# M-LVDS_PHY.net
KiCad netlist of a schematic drawn in Altium Designer
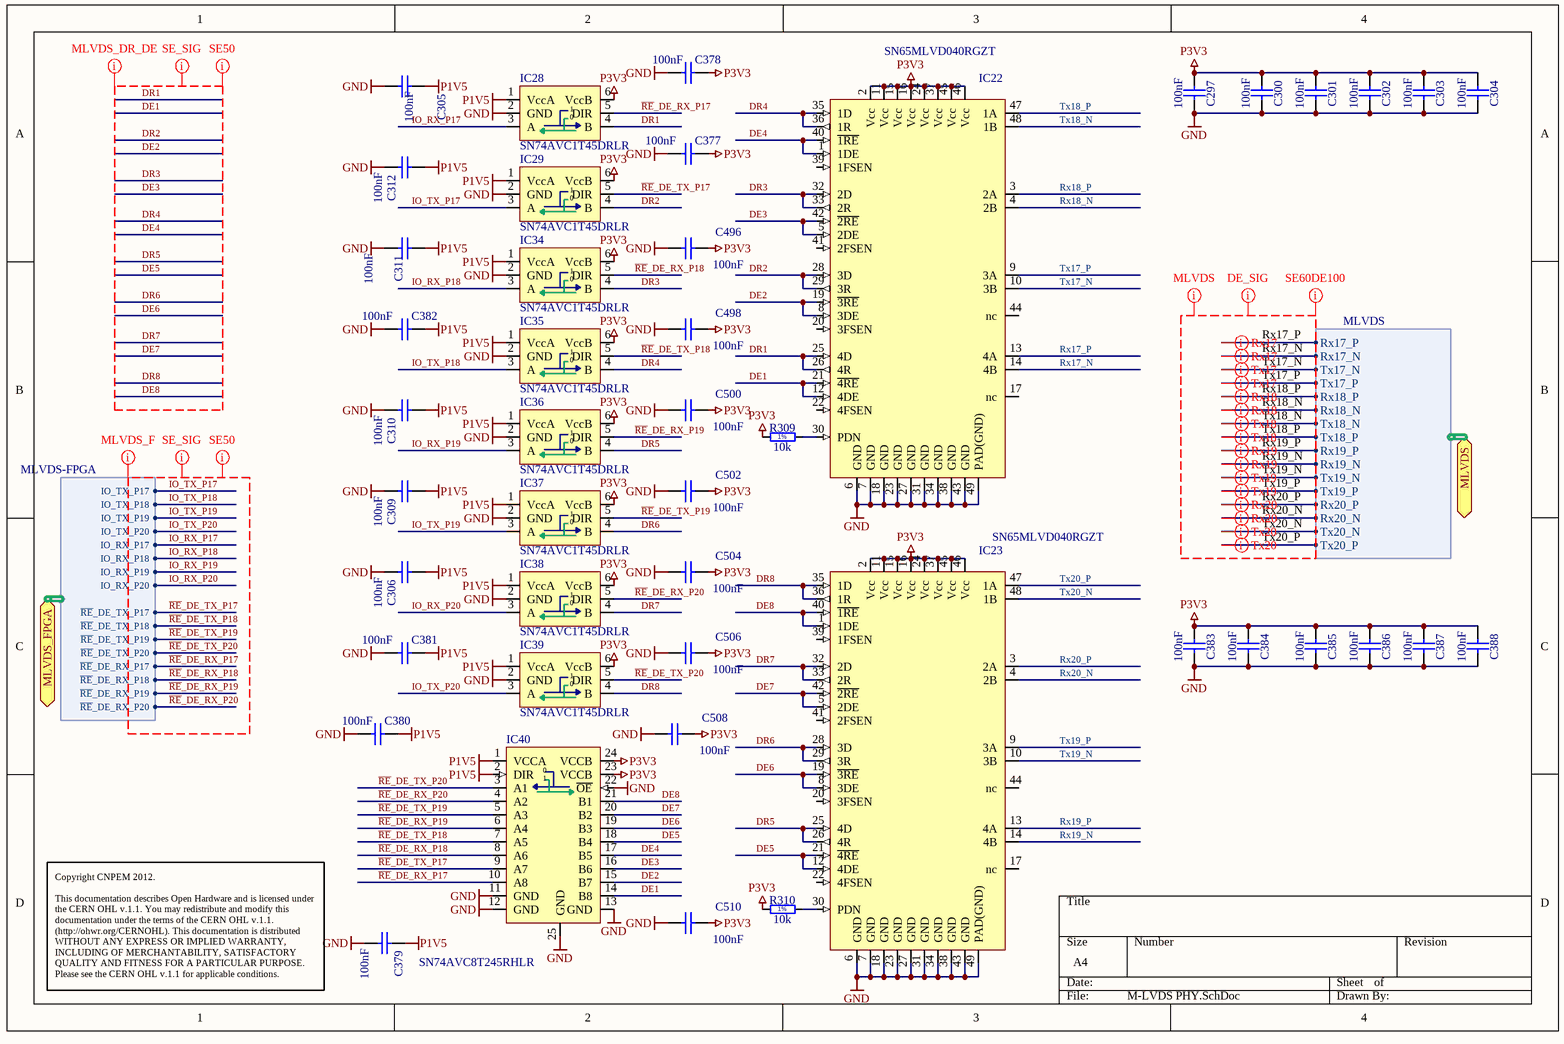
[diagram p0: M-LVDS PHY.SchDoc]

(export (version "E")
  (design (tool "Eeschema 10.0.6"))
  (components
    (comp (ref "C297")
      (value "100nF")
      (footprint "CAPC0603X33N")
      (description "Non-polarised capacitor")
      (fields
        (field (name "PART NUMBER") "CC0201_100NF_6.3V_10%_X5R")
        (field (name "VOLTAGE") "6.3V")
        (field (name "AUTHOR") "CERN DEM JLC")
      )
      (libsource (lib "Capacitors") (part "Capacitor - non polarized"))
    )
    (comp (ref "C300")
      (value "100nF")
      (footprint "CAPC0603X33N")
      (description "Non-polarised capacitor")
      (fields
        (field (name "PART NUMBER") "CC0201_100NF_6.3V_10%_X5R")
        (field (name "VOLTAGE") "6.3V")
        (field (name "AUTHOR") "CERN DEM JLC")
      )
      (libsource (lib "Capacitors") (part "Capacitor - non polarized"))
    )
    (comp (ref "C301")
      (value "100nF")
      (footprint "CAPC0603X33N")
      (description "Non-polarised capacitor")
      (fields
        (field (name "PART NUMBER") "CC0201_100NF_6.3V_10%_X5R")
        (field (name "VOLTAGE") "6.3V")
        (field (name "AUTHOR") "CERN DEM JLC")
      )
      (libsource (lib "Capacitors") (part "Capacitor - non polarized"))
    )
    (comp (ref "C302")
      (value "100nF")
      (footprint "CAPC0603X33N")
      (description "Non-polarised capacitor")
      (fields
        (field (name "PART NUMBER") "CC0201_100NF_6.3V_10%_X5R")
        (field (name "VOLTAGE") "6.3V")
        (field (name "AUTHOR") "CERN DEM JLC")
      )
      (libsource (lib "Capacitors") (part "Capacitor - non polarized"))
    )
    (comp (ref "C303")
      (value "100nF")
      (footprint "CAPC0603X33N")
      (description "Non-polarised capacitor")
      (fields
        (field (name "PART NUMBER") "CC0201_100NF_6.3V_10%_X5R")
        (field (name "VOLTAGE") "6.3V")
        (field (name "AUTHOR") "CERN DEM JLC")
      )
      (libsource (lib "Capacitors") (part "Capacitor - non polarized"))
    )
    (comp (ref "C304")
      (value "100nF")
      (footprint "CAPC0603X33N")
      (description "Non-polarised capacitor")
      (fields
        (field (name "PART NUMBER") "CC0201_100NF_6.3V_10%_X5R")
        (field (name "VOLTAGE") "6.3V")
        (field (name "AUTHOR") "CERN DEM JLC")
      )
      (libsource (lib "Capacitors") (part "Capacitor - non polarized"))
    )
    (comp (ref "C305")
      (value "100nF")
      (footprint "CAPC0603X33N")
      (description "Non-polarised capacitor")
      (fields
        (field (name "PART NUMBER") "CC0201_100NF_6.3V_10%_X5R")
        (field (name "VOLTAGE") "6.3V")
        (field (name "AUTHOR") "CERN DEM JLC")
      )
      (libsource (lib "Capacitors") (part "Capacitor - non polarized"))
    )
    (comp (ref "C306")
      (value "100nF")
      (footprint "CAPC0603X33N")
      (description "Non-polarised capacitor")
      (fields
        (field (name "PART NUMBER") "CC0201_100NF_6.3V_10%_X5R")
        (field (name "VOLTAGE") "6.3V")
        (field (name "AUTHOR") "CERN DEM JLC")
      )
      (libsource (lib "Capacitors") (part "Capacitor - non polarized"))
    )
    (comp (ref "C309")
      (value "100nF")
      (footprint "CAPC0603X33N")
      (description "Non-polarised capacitor")
      (fields
        (field (name "PART NUMBER") "CC0201_100NF_6.3V_10%_X5R")
        (field (name "VOLTAGE") "6.3V")
        (field (name "AUTHOR") "CERN DEM JLC")
      )
      (libsource (lib "Capacitors") (part "Capacitor - non polarized"))
    )
    (comp (ref "C310")
      (value "100nF")
      (footprint "CAPC0603X33N")
      (description "Non-polarised capacitor")
      (fields
        (field (name "PART NUMBER") "CC0201_100NF_6.3V_10%_X5R")
        (field (name "VOLTAGE") "6.3V")
        (field (name "AUTHOR") "CERN DEM JLC")
      )
      (libsource (lib "Capacitors") (part "Capacitor - non polarized"))
    )
    (comp (ref "C311")
      (value "100nF")
      (footprint "CAPC0603X33N")
      (description "Non-polarised capacitor")
      (fields
        (field (name "PART NUMBER") "CC0201_100NF_6.3V_10%_X5R")
        (field (name "VOLTAGE") "6.3V")
        (field (name "AUTHOR") "CERN DEM JLC")
      )
      (libsource (lib "Capacitors") (part "Capacitor - non polarized"))
    )
    (comp (ref "C312")
      (value "100nF")
      (footprint "CAPC0603X33N")
      (description "Non-polarised capacitor")
      (fields
        (field (name "PART NUMBER") "CC0201_100NF_6.3V_10%_X5R")
        (field (name "VOLTAGE") "6.3V")
        (field (name "AUTHOR") "CERN DEM JLC")
      )
      (libsource (lib "Capacitors") (part "Capacitor - non polarized"))
    )
    (comp (ref "C377")
      (value "100nF")
      (footprint "CAPC0603X33N")
      (description "Non-polarised capacitor")
      (fields
        (field (name "PART NUMBER") "CC0201_100NF_6.3V_10%_X5R")
        (field (name "VOLTAGE") "6.3V")
        (field (name "AUTHOR") "CERN DEM JLC")
      )
      (libsource (lib "Capacitors") (part "Capacitor - non polarized"))
    )
    (comp (ref "C378")
      (value "100nF")
      (footprint "CAPC0603X33N")
      (description "Non-polarised capacitor")
      (fields
        (field (name "PART NUMBER") "CC0201_100NF_6.3V_10%_X5R")
        (field (name "VOLTAGE") "6.3V")
        (field (name "AUTHOR") "CERN DEM JLC")
      )
      (libsource (lib "Capacitors") (part "Capacitor - non polarized"))
    )
    (comp (ref "C379")
      (value "100nF")
      (footprint "CAPC0603X33N")
      (description "Non-polarised capacitor")
      (fields
        (field (name "PART NUMBER") "CC0201_100NF_6.3V_10%_X5R")
        (field (name "VOLTAGE") "6.3V")
        (field (name "AUTHOR") "CERN DEM JLC")
      )
      (libsource (lib "Capacitors") (part "Capacitor - non polarized"))
    )
    (comp (ref "C380")
      (value "100nF")
      (footprint "CAPC0603X33N")
      (description "Non-polarised capacitor")
      (fields
        (field (name "PART NUMBER") "CC0201_100NF_6.3V_10%_X5R")
        (field (name "VOLTAGE") "6.3V")
        (field (name "AUTHOR") "CERN DEM JLC")
      )
      (libsource (lib "Capacitors") (part "Capacitor - non polarized"))
    )
    (comp (ref "C381")
      (value "100nF")
      (footprint "CAPC0603X33N")
      (description "Non-polarised capacitor")
      (fields
        (field (name "PART NUMBER") "CC0201_100NF_6.3V_10%_X5R")
        (field (name "VOLTAGE") "6.3V")
        (field (name "AUTHOR") "CERN DEM JLC")
      )
      (libsource (lib "Capacitors") (part "Capacitor - non polarized"))
    )
    (comp (ref "C382")
      (value "100nF")
      (footprint "CAPC0603X33N")
      (description "Non-polarised capacitor")
      (fields
        (field (name "PART NUMBER") "CC0201_100NF_6.3V_10%_X5R")
        (field (name "VOLTAGE") "6.3V")
        (field (name "AUTHOR") "CERN DEM JLC")
      )
      (libsource (lib "Capacitors") (part "Capacitor - non polarized"))
    )
    (comp (ref "C383")
      (value "100nF")
      (footprint "CAPC0603X33N")
      (description "Non-polarised capacitor")
      (fields
        (field (name "PART NUMBER") "CC0201_100NF_6.3V_10%_X5R")
        (field (name "VOLTAGE") "6.3V")
        (field (name "AUTHOR") "CERN DEM JLC")
      )
      (libsource (lib "Capacitors") (part "Capacitor - non polarized"))
    )
    (comp (ref "C384")
      (value "100nF")
      (footprint "CAPC0603X33N")
      (description "Non-polarised capacitor")
      (fields
        (field (name "PART NUMBER") "CC0201_100NF_6.3V_10%_X5R")
        (field (name "VOLTAGE") "6.3V")
        (field (name "AUTHOR") "CERN DEM JLC")
      )
      (libsource (lib "Capacitors") (part "Capacitor - non polarized"))
    )
    (comp (ref "C385")
      (value "100nF")
      (footprint "CAPC0603X33N")
      (description "Non-polarised capacitor")
      (fields
        (field (name "PART NUMBER") "CC0201_100NF_6.3V_10%_X5R")
        (field (name "VOLTAGE") "6.3V")
        (field (name "AUTHOR") "CERN DEM JLC")
      )
      (libsource (lib "Capacitors") (part "Capacitor - non polarized"))
    )
    (comp (ref "C386")
      (value "100nF")
      (footprint "CAPC0603X33N")
      (description "Non-polarised capacitor")
      (fields
        (field (name "PART NUMBER") "CC0201_100NF_6.3V_10%_X5R")
        (field (name "VOLTAGE") "6.3V")
        (field (name "AUTHOR") "CERN DEM JLC")
      )
      (libsource (lib "Capacitors") (part "Capacitor - non polarized"))
    )
    (comp (ref "C387")
      (value "100nF")
      (footprint "CAPC0603X33N")
      (description "Non-polarised capacitor")
      (fields
        (field (name "PART NUMBER") "CC0201_100NF_6.3V_10%_X5R")
        (field (name "VOLTAGE") "6.3V")
        (field (name "AUTHOR") "CERN DEM JLC")
      )
      (libsource (lib "Capacitors") (part "Capacitor - non polarized"))
    )
    (comp (ref "C388")
      (value "100nF")
      (footprint "CAPC0603X33N")
      (description "Non-polarised capacitor")
      (fields
        (field (name "PART NUMBER") "CC0201_100NF_6.3V_10%_X5R")
        (field (name "VOLTAGE") "6.3V")
        (field (name "AUTHOR") "CERN DEM JLC")
      )
      (libsource (lib "Capacitors") (part "Capacitor - non polarized"))
    )
    (comp (ref "C496")
      (value "100nF")
      (footprint "CAPC0603X33N")
      (description "Non-polarised capacitor")
      (fields
        (field (name "PART NUMBER") "CC0201_100NF_6.3V_10%_X5R")
        (field (name "VOLTAGE") "6.3V")
        (field (name "AUTHOR") "CERN DEM JLC")
      )
      (libsource (lib "Capacitors") (part "Capacitor - non polarized"))
    )
    (comp (ref "C498")
      (value "100nF")
      (footprint "CAPC0603X33N")
      (description "Non-polarised capacitor")
      (fields
        (field (name "PART NUMBER") "CC0201_100NF_6.3V_10%_X5R")
        (field (name "VOLTAGE") "6.3V")
        (field (name "AUTHOR") "CERN DEM JLC")
      )
      (libsource (lib "Capacitors") (part "Capacitor - non polarized"))
    )
    (comp (ref "C500")
      (value "100nF")
      (footprint "CAPC0603X33N")
      (description "Non-polarised capacitor")
      (fields
        (field (name "PART NUMBER") "CC0201_100NF_6.3V_10%_X5R")
        (field (name "VOLTAGE") "6.3V")
        (field (name "AUTHOR") "CERN DEM JLC")
      )
      (libsource (lib "Capacitors") (part "Capacitor - non polarized"))
    )
    (comp (ref "C502")
      (value "100nF")
      (footprint "CAPC0603X33N")
      (description "Non-polarised capacitor")
      (fields
        (field (name "PART NUMBER") "CC0201_100NF_6.3V_10%_X5R")
        (field (name "VOLTAGE") "6.3V")
        (field (name "AUTHOR") "CERN DEM JLC")
      )
      (libsource (lib "Capacitors") (part "Capacitor - non polarized"))
    )
    (comp (ref "C504")
      (value "100nF")
      (footprint "CAPC0603X33N")
      (description "Non-polarised capacitor")
      (fields
        (field (name "PART NUMBER") "CC0201_100NF_6.3V_10%_X5R")
        (field (name "VOLTAGE") "6.3V")
        (field (name "AUTHOR") "CERN DEM JLC")
      )
      (libsource (lib "Capacitors") (part "Capacitor - non polarized"))
    )
    (comp (ref "C506")
      (value "100nF")
      (footprint "CAPC0603X33N")
      (description "Non-polarised capacitor")
      (fields
        (field (name "PART NUMBER") "CC0201_100NF_6.3V_10%_X5R")
        (field (name "VOLTAGE") "6.3V")
        (field (name "AUTHOR") "CERN DEM JLC")
      )
      (libsource (lib "Capacitors") (part "Capacitor - non polarized"))
    )
    (comp (ref "C508")
      (value "100nF")
      (footprint "CAPC0603X33N")
      (description "Non-polarised capacitor")
      (fields
        (field (name "PART NUMBER") "CC0201_100NF_6.3V_10%_X5R")
        (field (name "VOLTAGE") "6.3V")
        (field (name "AUTHOR") "CERN DEM JLC")
      )
      (libsource (lib "Capacitors") (part "Capacitor - non polarized"))
    )
    (comp (ref "C510")
      (value "100nF")
      (footprint "CAPC0603X33N")
      (description "Non-polarised capacitor")
      (fields
        (field (name "PART NUMBER") "CC0201_100NF_6.3V_10%_X5R")
        (field (name "VOLTAGE") "6.3V")
        (field (name "AUTHOR") "CERN DEM JLC")
      )
      (libsource (lib "Capacitors") (part "Capacitor - non polarized"))
    )
    (comp (ref "IC22")
      (value "SN65MLVD040RGZT")
      (footprint "QFN48L")
      (libsource (lib "LIBRARY_SCH") (part "IFC_SN65MLVD040"))
    )
    (comp (ref "IC23")
      (value "SN65MLVD040RGZT")
      (footprint "QFN48L")
      (libsource (lib "LIBRARY_SCH") (part "IFC_SN65MLVD040"))
    )
    (comp (ref "IC28")
      (value "SN74AVC1T45DRLR")
      (footprint "SOT-553")
      (description "1-bit Transceiver Dual Supply (1.4...3.6V)")
      (libsource (lib "LIBRARY_SCH") (part "74AVC1T45"))
    )
    (comp (ref "IC29")
      (value "SN74AVC1T45DRLR")
      (footprint "SOT-553")
      (description "1-bit Transceiver Dual Supply (1.4...3.6V)")
      (libsource (lib "LIBRARY_SCH") (part "74AVC1T45"))
    )
    (comp (ref "IC34")
      (value "SN74AVC1T45DRLR")
      (footprint "SOT-553")
      (description "1-bit Transceiver Dual Supply (1.4...3.6V)")
      (libsource (lib "LIBRARY_SCH") (part "74AVC1T45"))
    )
    (comp (ref "IC35")
      (value "SN74AVC1T45DRLR")
      (footprint "SOT-553")
      (description "1-bit Transceiver Dual Supply (1.4...3.6V)")
      (libsource (lib "LIBRARY_SCH") (part "74AVC1T45"))
    )
    (comp (ref "IC36")
      (value "SN74AVC1T45DRLR")
      (footprint "SOT-553")
      (description "1-bit Transceiver Dual Supply (1.4...3.6V)")
      (libsource (lib "LIBRARY_SCH") (part "74AVC1T45"))
    )
    (comp (ref "IC37")
      (value "SN74AVC1T45DRLR")
      (footprint "SOT-553")
      (description "1-bit Transceiver Dual Supply (1.4...3.6V)")
      (libsource (lib "LIBRARY_SCH") (part "74AVC1T45"))
    )
    (comp (ref "IC38")
      (value "SN74AVC1T45DRLR")
      (footprint "SOT-553")
      (description "1-bit Transceiver Dual Supply (1.4...3.6V)")
      (libsource (lib "LIBRARY_SCH") (part "74AVC1T45"))
    )
    (comp (ref "IC39")
      (value "SN74AVC1T45DRLR")
      (footprint "SOT-553")
      (description "1-bit Transceiver Dual Supply (1.4...3.6V)")
      (libsource (lib "LIBRARY_SCH") (part "74AVC1T45"))
    )
    (comp (ref "IC40")
      (value "SN74AVC8T245RHLR")
      (footprint "QFN50P350X550X100-24N")
      (description "8 channel bidir translator buffer (1.4..3.6V)")
      (libsource (lib "LIBRARY_SCH") (part "74AVC8T245_QFN"))
    )
    (comp (ref "R309")
      (value "10k")
      (footprint "RESC1005X40N")
      (description "Resistor - 1%")
      (fields
        (field (name "PART NUMBER") "R0402_10K_1%_0.0625W_100PPM")
        (field (name "POWER") "0.0625W")
        (field (name "AUTHOR") "CERN DEM JLC")
      )
      (libsource (lib "Resistors") (part "Resistor - 1%"))
    )
    (comp (ref "R310")
      (value "10k")
      (footprint "RESC1005X40N")
      (description "Resistor - 1%")
      (fields
        (field (name "PART NUMBER") "R0402_10K_1%_0.0625W_100PPM")
        (field (name "POWER") "0.0625W")
        (field (name "AUTHOR") "CERN DEM JLC")
      )
      (libsource (lib "Resistors") (part "Resistor - 1%"))
    )
  )
  (nets
    (net (code "3") (name "/DE1") (class "Default")
      (node (ref "IC22") (pin "12") (pinfunction "4DE_12") (pintype "input"))
      (node (ref "IC22") (pin "21") (pinfunction "~{4RE}_21") (pintype "input"))
      (node (ref "IC40") (pin "14") (pinfunction "B8_14") (pintype "bidirectional"))
    )
    (net (code "4") (name "/DE2") (class "Default")
      (node (ref "IC22") (pin "19") (pinfunction "~{3RE}_19") (pintype "input"))
      (node (ref "IC22") (pin "8") (pinfunction "3DE_8") (pintype "input"))
      (node (ref "IC40") (pin "15") (pinfunction "B7_15") (pintype "bidirectional"))
    )
    (net (code "5") (name "/DE3") (class "Default")
      (node (ref "IC22") (pin "42") (pinfunction "~{2RE}_42") (pintype "input"))
      (node (ref "IC22") (pin "5") (pinfunction "2DE_5") (pintype "input"))
      (node (ref "IC40") (pin "16") (pinfunction "B6_16") (pintype "bidirectional"))
    )
    (net (code "6") (name "/DE4") (class "Default")
      (node (ref "IC22") (pin "1") (pinfunction "1DE_1") (pintype "input"))
      (node (ref "IC22") (pin "40") (pinfunction "~{1RE}_40") (pintype "input"))
      (node (ref "IC40") (pin "17") (pinfunction "B5_17") (pintype "bidirectional"))
    )
    (net (code "7") (name "/DE5") (class "Default")
      (node (ref "IC23") (pin "12") (pinfunction "4DE_12") (pintype "input"))
      (node (ref "IC23") (pin "21") (pinfunction "~{4RE}_21") (pintype "input"))
      (node (ref "IC40") (pin "18") (pinfunction "B4_18") (pintype "bidirectional"))
    )
    (net (code "8") (name "/DE6") (class "Default")
      (node (ref "IC23") (pin "19") (pinfunction "~{3RE}_19") (pintype "input"))
      (node (ref "IC23") (pin "8") (pinfunction "3DE_8") (pintype "input"))
      (node (ref "IC40") (pin "19") (pinfunction "B3_19") (pintype "bidirectional"))
    )
    (net (code "9") (name "/DE7") (class "Default")
      (node (ref "IC23") (pin "42") (pinfunction "~{2RE}_42") (pintype "input"))
      (node (ref "IC23") (pin "5") (pinfunction "2DE_5") (pintype "input"))
      (node (ref "IC40") (pin "20") (pinfunction "B2_20") (pintype "bidirectional"))
    )
    (net (code "10") (name "/DE8") (class "Default")
      (node (ref "IC23") (pin "1") (pinfunction "1DE_1") (pintype "input"))
      (node (ref "IC23") (pin "40") (pinfunction "~{1RE}_40") (pintype "input"))
      (node (ref "IC40") (pin "21") (pinfunction "B1_21") (pintype "bidirectional"))
    )
    (net (code "11") (name "/DR1") (class "Default")
      (node (ref "IC22") (pin "25") (pinfunction "4D_25") (pintype "input"))
      (node (ref "IC22") (pin "26") (pinfunction "4R_26") (pintype "output"))
      (node (ref "IC28") (pin "4") (pinfunction "B_4") (pintype "passive"))
    )
    (net (code "12") (name "/DR2") (class "Default")
      (node (ref "IC22") (pin "28") (pinfunction "3D_28") (pintype "input"))
      (node (ref "IC22") (pin "29") (pinfunction "3R_29") (pintype "output"))
      (node (ref "IC29") (pin "4") (pinfunction "B_4") (pintype "passive"))
    )
    (net (code "13") (name "/DR3") (class "Default")
      (node (ref "IC22") (pin "32") (pinfunction "2D_32") (pintype "input"))
      (node (ref "IC22") (pin "33") (pinfunction "2R_33") (pintype "output"))
      (node (ref "IC34") (pin "4") (pinfunction "B_4") (pintype "passive"))
    )
    (net (code "14") (name "/DR4") (class "Default")
      (node (ref "IC22") (pin "35") (pinfunction "1D_35") (pintype "input"))
      (node (ref "IC22") (pin "36") (pinfunction "1R_36") (pintype "output"))
      (node (ref "IC35") (pin "4") (pinfunction "B_4") (pintype "passive"))
    )
    (net (code "15") (name "/DR5") (class "Default")
      (node (ref "IC23") (pin "25") (pinfunction "4D_25") (pintype "input"))
      (node (ref "IC23") (pin "26") (pinfunction "4R_26") (pintype "output"))
      (node (ref "IC36") (pin "4") (pinfunction "B_4") (pintype "passive"))
    )
    (net (code "16") (name "/DR6") (class "Default")
      (node (ref "IC23") (pin "28") (pinfunction "3D_28") (pintype "input"))
      (node (ref "IC23") (pin "29") (pinfunction "3R_29") (pintype "output"))
      (node (ref "IC37") (pin "4") (pinfunction "B_4") (pintype "passive"))
    )
    (net (code "17") (name "/DR7") (class "Default")
      (node (ref "IC23") (pin "32") (pinfunction "2D_32") (pintype "input"))
      (node (ref "IC23") (pin "33") (pinfunction "2R_33") (pintype "output"))
      (node (ref "IC38") (pin "4") (pinfunction "B_4") (pintype "passive"))
    )
    (net (code "18") (name "/DR8") (class "Default")
      (node (ref "IC23") (pin "35") (pinfunction "1D_35") (pintype "input"))
      (node (ref "IC23") (pin "36") (pinfunction "1R_36") (pintype "output"))
      (node (ref "IC39") (pin "4") (pinfunction "B_4") (pintype "passive"))
    )
    (net (code "19") (name "/IO_RX_P17") (class "Default")
      (node (ref "IC28") (pin "3") (pinfunction "A_3") (pintype "passive"))
    )
    (net (code "20") (name "/IO_RX_P18") (class "Default")
      (node (ref "IC34") (pin "3") (pinfunction "A_3") (pintype "passive"))
    )
    (net (code "21") (name "/IO_RX_P19") (class "Default")
      (node (ref "IC36") (pin "3") (pinfunction "A_3") (pintype "passive"))
    )
    (net (code "22") (name "/IO_RX_P20") (class "Default")
      (node (ref "IC38") (pin "3") (pinfunction "A_3") (pintype "passive"))
    )
    (net (code "23") (name "/IO_TX_P17") (class "Default")
      (node (ref "IC29") (pin "3") (pinfunction "A_3") (pintype "passive"))
    )
    (net (code "24") (name "/IO_TX_P18") (class "Default")
      (node (ref "IC35") (pin "3") (pinfunction "A_3") (pintype "passive"))
    )
    (net (code "25") (name "/IO_TX_P19") (class "Default")
      (node (ref "IC37") (pin "3") (pinfunction "A_3") (pintype "passive"))
    )
    (net (code "26") (name "/IO_TX_P20") (class "Default")
      (node (ref "IC39") (pin "3") (pinfunction "A_3") (pintype "passive"))
    )
    (net (code "27") (name "/Rx17_N") (class "Default")
      (node (ref "IC22") (pin "14") (pinfunction "4B_14") (pintype "bidirectional"))
    )
    (net (code "28") (name "/Rx17_P") (class "Default")
      (node (ref "IC22") (pin "13") (pinfunction "4A_13") (pintype "bidirectional"))
    )
    (net (code "29") (name "/Rx18_N") (class "Default")
      (node (ref "IC22") (pin "4") (pinfunction "2B_4") (pintype "bidirectional"))
    )
    (net (code "30") (name "/Rx18_P") (class "Default")
      (node (ref "IC22") (pin "3") (pinfunction "2A_3") (pintype "bidirectional"))
    )
    (net (code "31") (name "/Rx19_N") (class "Default")
      (node (ref "IC23") (pin "14") (pinfunction "4B_14") (pintype "bidirectional"))
    )
    (net (code "32") (name "/Rx19_P") (class "Default")
      (node (ref "IC23") (pin "13") (pinfunction "4A_13") (pintype "bidirectional"))
    )
    (net (code "33") (name "/Rx20_N") (class "Default")
      (node (ref "IC23") (pin "4") (pinfunction "2B_4") (pintype "bidirectional"))
    )
    (net (code "34") (name "/Rx20_P") (class "Default")
      (node (ref "IC23") (pin "3") (pinfunction "2A_3") (pintype "bidirectional"))
    )
    (net (code "35") (name "/Tx17_N") (class "Default")
      (node (ref "IC22") (pin "10") (pinfunction "3B_10") (pintype "bidirectional"))
    )
    (net (code "36") (name "/Tx17_P") (class "Default")
      (node (ref "IC22") (pin "9") (pinfunction "3A_9") (pintype "bidirectional"))
    )
    (net (code "37") (name "/Tx18_N") (class "Default")
      (node (ref "IC22") (pin "48") (pinfunction "1B_48") (pintype "bidirectional"))
    )
    (net (code "38") (name "/Tx18_P") (class "Default")
      (node (ref "IC22") (pin "47") (pinfunction "1A_47") (pintype "bidirectional"))
    )
    (net (code "39") (name "/Tx19_N") (class "Default")
      (node (ref "IC23") (pin "10") (pinfunction "3B_10") (pintype "bidirectional"))
    )
    (net (code "40") (name "/Tx19_P") (class "Default")
      (node (ref "IC23") (pin "9") (pinfunction "3A_9") (pintype "bidirectional"))
    )
    (net (code "41") (name "/Tx20_N") (class "Default")
      (node (ref "IC23") (pin "48") (pinfunction "1B_48") (pintype "bidirectional"))
    )
    (net (code "42") (name "/Tx20_P") (class "Default")
      (node (ref "IC23") (pin "47") (pinfunction "1A_47") (pintype "bidirectional"))
    )
    (net (code "45") (name "/~{RE}_DE_RX_P17") (class "Default")
      (node (ref "IC28") (pin "5") (pinfunction "DIR_5") (pintype "passive"))
      (node (ref "IC40") (pin "10") (pinfunction "A8_10") (pintype "bidirectional"))
    )
    (net (code "46") (name "/~{RE}_DE_RX_P18") (class "Default")
      (node (ref "IC34") (pin "5") (pinfunction "DIR_5") (pintype "passive"))
      (node (ref "IC40") (pin "8") (pinfunction "A6_8") (pintype "bidirectional"))
    )
    (net (code "47") (name "/~{RE}_DE_RX_P19") (class "Default")
      (node (ref "IC36") (pin "5") (pinfunction "DIR_5") (pintype "passive"))
      (node (ref "IC40") (pin "6") (pinfunction "A4_6") (pintype "bidirectional"))
    )
    (net (code "48") (name "/~{RE}_DE_RX_P20") (class "Default")
      (node (ref "IC38") (pin "5") (pinfunction "DIR_5") (pintype "passive"))
      (node (ref "IC40") (pin "4") (pinfunction "A2_4") (pintype "bidirectional"))
    )
    (net (code "49") (name "/~{RE}_DE_TX_P17") (class "Default")
      (node (ref "IC29") (pin "5") (pinfunction "DIR_5") (pintype "passive"))
      (node (ref "IC40") (pin "9") (pinfunction "A7_9") (pintype "bidirectional"))
    )
    (net (code "50") (name "/~{RE}_DE_TX_P18") (class "Default")
      (node (ref "IC35") (pin "5") (pinfunction "DIR_5") (pintype "passive"))
      (node (ref "IC40") (pin "7") (pinfunction "A5_7") (pintype "bidirectional"))
    )
    (net (code "51") (name "/~{RE}_DE_TX_P19") (class "Default")
      (node (ref "IC37") (pin "5") (pinfunction "DIR_5") (pintype "passive"))
      (node (ref "IC40") (pin "5") (pinfunction "A3_5") (pintype "bidirectional"))
    )
    (net (code "52") (name "/~{RE}_DE_TX_P20") (class "Default")
      (node (ref "IC39") (pin "5") (pinfunction "DIR_5") (pintype "passive"))
      (node (ref "IC40") (pin "3") (pinfunction "A1_3") (pintype "bidirectional"))
    )
    (net (code "53") (name "GND") (class "Default")
      (node (ref "C297") (pin "2") (pinfunction "2_2") (pintype "passive"))
      (node (ref "C300") (pin "2") (pinfunction "2_2") (pintype "passive"))
      (node (ref "C301") (pin "2") (pinfunction "2_2") (pintype "passive"))
      (node (ref "C302") (pin "2") (pinfunction "2_2") (pintype "passive"))
      (node (ref "C303") (pin "2") (pinfunction "2_2") (pintype "passive"))
      (node (ref "C304") (pin "2") (pinfunction "2_2") (pintype "passive"))
      (node (ref "C305") (pin "2") (pinfunction "2_2") (pintype "passive"))
      (node (ref "C306") (pin "1") (pinfunction "1_1") (pintype "passive"))
      (node (ref "C309") (pin "1") (pinfunction "1_1") (pintype "passive"))
      (node (ref "C310") (pin "1") (pinfunction "1_1") (pintype "passive"))
      (node (ref "C311") (pin "1") (pinfunction "1_1") (pintype "passive"))
      (node (ref "C312") (pin "1") (pinfunction "1_1") (pintype "passive"))
      (node (ref "C377") (pin "1") (pinfunction "1_1") (pintype "passive"))
      (node (ref "C378") (pin "1") (pinfunction "1_1") (pintype "passive"))
      (node (ref "C379") (pin "1") (pinfunction "1_1") (pintype "passive"))
      (node (ref "C380") (pin "1") (pinfunction "1_1") (pintype "passive"))
      (node (ref "C381") (pin "1") (pinfunction "1_1") (pintype "passive"))
      (node (ref "C382") (pin "1") (pinfunction "1_1") (pintype "passive"))
      (node (ref "C383") (pin "2") (pinfunction "2_2") (pintype "passive"))
      (node (ref "C384") (pin "2") (pinfunction "2_2") (pintype "passive"))
      (node (ref "C385") (pin "2") (pinfunction "2_2") (pintype "passive"))
      (node (ref "C386") (pin "2") (pinfunction "2_2") (pintype "passive"))
      (node (ref "C387") (pin "2") (pinfunction "2_2") (pintype "passive"))
      (node (ref "C388") (pin "2") (pinfunction "2_2") (pintype "passive"))
      (node (ref "C496") (pin "2") (pinfunction "2_2") (pintype "passive"))
      (node (ref "C498") (pin "2") (pinfunction "2_2") (pintype "passive"))
      (node (ref "C500") (pin "2") (pinfunction "2_2") (pintype "passive"))
      (node (ref "C502") (pin "2") (pinfunction "2_2") (pintype "passive"))
      (node (ref "C504") (pin "2") (pinfunction "2_2") (pintype "passive"))
      (node (ref "C506") (pin "2") (pinfunction "2_2") (pintype "passive"))
      (node (ref "C508") (pin "2") (pinfunction "2_2") (pintype "passive"))
      (node (ref "C510") (pin "2") (pinfunction "2_2") (pintype "passive"))
      (node (ref "IC22") (pin "18") (pinfunction "GND_18") (pintype "power_in"))
      (node (ref "IC22") (pin "23") (pinfunction "GND_23") (pintype "power_in"))
      (node (ref "IC22") (pin "27") (pinfunction "GND_27") (pintype "power_in"))
      (node (ref "IC22") (pin "31") (pinfunction "GND_31") (pintype "power_in"))
      (node (ref "IC22") (pin "34") (pinfunction "GND_34") (pintype "power_in"))
      (node (ref "IC22") (pin "38") (pinfunction "GND_38") (pintype "power_in"))
      (node (ref "IC22") (pin "43") (pinfunction "GND_43") (pintype "power_in"))
      (node (ref "IC22") (pin "49") (pinfunction "PAD(GND)_49") (pintype "power_in"))
      (node (ref "IC22") (pin "6") (pinfunction "GND_6") (pintype "power_in"))
      (node (ref "IC22") (pin "7") (pinfunction "GND_7") (pintype "power_in"))
      (node (ref "IC23") (pin "18") (pinfunction "GND_18") (pintype "power_in"))
      (node (ref "IC23") (pin "23") (pinfunction "GND_23") (pintype "power_in"))
      (node (ref "IC23") (pin "27") (pinfunction "GND_27") (pintype "power_in"))
      (node (ref "IC23") (pin "31") (pinfunction "GND_31") (pintype "power_in"))
      (node (ref "IC23") (pin "34") (pinfunction "GND_34") (pintype "power_in"))
      (node (ref "IC23") (pin "38") (pinfunction "GND_38") (pintype "power_in"))
      (node (ref "IC23") (pin "43") (pinfunction "GND_43") (pintype "power_in"))
      (node (ref "IC23") (pin "49") (pinfunction "PAD(GND)_49") (pintype "power_in"))
      (node (ref "IC23") (pin "6") (pinfunction "GND_6") (pintype "power_in"))
      (node (ref "IC23") (pin "7") (pinfunction "GND_7") (pintype "power_in"))
      (node (ref "IC28") (pin "2") (pinfunction "GND_2") (pintype "passive"))
      (node (ref "IC29") (pin "2") (pinfunction "GND_2") (pintype "passive"))
      (node (ref "IC34") (pin "2") (pinfunction "GND_2") (pintype "passive"))
      (node (ref "IC35") (pin "2") (pinfunction "GND_2") (pintype "passive"))
      (node (ref "IC36") (pin "2") (pinfunction "GND_2") (pintype "passive"))
      (node (ref "IC37") (pin "2") (pinfunction "GND_2") (pintype "passive"))
      (node (ref "IC38") (pin "2") (pinfunction "GND_2") (pintype "passive"))
      (node (ref "IC39") (pin "2") (pinfunction "GND_2") (pintype "passive"))
      (node (ref "IC40") (pin "11") (pinfunction "GND_11") (pintype "power_in"))
      (node (ref "IC40") (pin "12") (pinfunction "GND_12") (pintype "power_in"))
      (node (ref "IC40") (pin "13") (pinfunction "GND_13") (pintype "power_in"))
      (node (ref "IC40") (pin "22") (pinfunction "~{OE}_22") (pintype "input"))
      (node (ref "IC40") (pin "25") (pinfunction "GND_25") (pintype "power_in"))
    )
    (net (code "54") (name "Net-(IC22-PDN)") (class "Default")
      (node (ref "IC22") (pin "30") (pinfunction "PDN_30") (pintype "input"))
      (node (ref "R309") (pin "2") (pinfunction "2_2") (pintype "passive"))
    )
    (net (code "55") (name "Net-(IC23-PDN)") (class "Default")
      (node (ref "IC23") (pin "30") (pinfunction "PDN_30") (pintype "input"))
      (node (ref "R310") (pin "2") (pinfunction "2_2") (pintype "passive"))
    )
    (net (code "56") (name "P1V5") (class "Default")
      (node (ref "C305") (pin "1") (pinfunction "1_1") (pintype "passive"))
      (node (ref "C306") (pin "2") (pinfunction "2_2") (pintype "passive"))
      (node (ref "C309") (pin "2") (pinfunction "2_2") (pintype "passive"))
      (node (ref "C310") (pin "2") (pinfunction "2_2") (pintype "passive"))
      (node (ref "C311") (pin "2") (pinfunction "2_2") (pintype "passive"))
      (node (ref "C312") (pin "2") (pinfunction "2_2") (pintype "passive"))
      (node (ref "C379") (pin "2") (pinfunction "2_2") (pintype "passive"))
      (node (ref "C380") (pin "2") (pinfunction "2_2") (pintype "passive"))
      (node (ref "C381") (pin "2") (pinfunction "2_2") (pintype "passive"))
      (node (ref "C382") (pin "2") (pinfunction "2_2") (pintype "passive"))
      (node (ref "IC28") (pin "1") (pinfunction "VccA_1") (pintype "power_in"))
      (node (ref "IC29") (pin "1") (pinfunction "VccA_1") (pintype "power_in"))
      (node (ref "IC34") (pin "1") (pinfunction "VccA_1") (pintype "power_in"))
      (node (ref "IC35") (pin "1") (pinfunction "VccA_1") (pintype "power_in"))
      (node (ref "IC36") (pin "1") (pinfunction "VccA_1") (pintype "power_in"))
      (node (ref "IC37") (pin "1") (pinfunction "VccA_1") (pintype "power_in"))
      (node (ref "IC38") (pin "1") (pinfunction "VccA_1") (pintype "power_in"))
      (node (ref "IC39") (pin "1") (pinfunction "VccA_1") (pintype "power_in"))
      (node (ref "IC40") (pin "1") (pinfunction "VCCA_1") (pintype "power_in"))
      (node (ref "IC40") (pin "2") (pinfunction "DIR_2") (pintype "input"))
    )
    (net (code "57") (name "P3V3") (class "Default")
      (node (ref "C297") (pin "1") (pinfunction "1_1") (pintype "passive"))
      (node (ref "C300") (pin "1") (pinfunction "1_1") (pintype "passive"))
      (node (ref "C301") (pin "1") (pinfunction "1_1") (pintype "passive"))
      (node (ref "C302") (pin "1") (pinfunction "1_1") (pintype "passive"))
      (node (ref "C303") (pin "1") (pinfunction "1_1") (pintype "passive"))
      (node (ref "C304") (pin "1") (pinfunction "1_1") (pintype "passive"))
      (node (ref "C377") (pin "2") (pinfunction "2_2") (pintype "passive"))
      (node (ref "C378") (pin "2") (pinfunction "2_2") (pintype "passive"))
      (node (ref "C383") (pin "1") (pinfunction "1_1") (pintype "passive"))
      (node (ref "C384") (pin "1") (pinfunction "1_1") (pintype "passive"))
      (node (ref "C385") (pin "1") (pinfunction "1_1") (pintype "passive"))
      (node (ref "C386") (pin "1") (pinfunction "1_1") (pintype "passive"))
      (node (ref "C387") (pin "1") (pinfunction "1_1") (pintype "passive"))
      (node (ref "C388") (pin "1") (pinfunction "1_1") (pintype "passive"))
      (node (ref "C496") (pin "1") (pinfunction "1_1") (pintype "passive"))
      (node (ref "C498") (pin "1") (pinfunction "1_1") (pintype "passive"))
      (node (ref "C500") (pin "1") (pinfunction "1_1") (pintype "passive"))
      (node (ref "C502") (pin "1") (pinfunction "1_1") (pintype "passive"))
      (node (ref "C504") (pin "1") (pinfunction "1_1") (pintype "passive"))
      (node (ref "C506") (pin "1") (pinfunction "1_1") (pintype "passive"))
      (node (ref "C508") (pin "1") (pinfunction "1_1") (pintype "passive"))
      (node (ref "C510") (pin "1") (pinfunction "1_1") (pintype "passive"))
      (node (ref "IC22") (pin "11") (pinfunction "Vcc_11") (pintype "power_in"))
      (node (ref "IC22") (pin "15") (pinfunction "Vcc_15") (pintype "power_in"))
      (node (ref "IC22") (pin "16") (pinfunction "Vcc_16") (pintype "power_in"))
      (node (ref "IC22") (pin "2") (pinfunction "Vcc_2") (pintype "power_in"))
      (node (ref "IC22") (pin "24") (pinfunction "Vcc_24") (pintype "power_in"))
      (node (ref "IC22") (pin "37") (pinfunction "Vcc_37") (pintype "power_in"))
      (node (ref "IC22") (pin "45") (pinfunction "Vcc_45") (pintype "power_in"))
      (node (ref "IC22") (pin "46") (pinfunction "Vcc_46") (pintype "power_in"))
      (node (ref "IC23") (pin "11") (pinfunction "Vcc_11") (pintype "power_in"))
      (node (ref "IC23") (pin "15") (pinfunction "Vcc_15") (pintype "power_in"))
      (node (ref "IC23") (pin "16") (pinfunction "Vcc_16") (pintype "power_in"))
      (node (ref "IC23") (pin "2") (pinfunction "Vcc_2") (pintype "power_in"))
      (node (ref "IC23") (pin "24") (pinfunction "Vcc_24") (pintype "power_in"))
      (node (ref "IC23") (pin "37") (pinfunction "Vcc_37") (pintype "power_in"))
      (node (ref "IC23") (pin "45") (pinfunction "Vcc_45") (pintype "power_in"))
      (node (ref "IC23") (pin "46") (pinfunction "Vcc_46") (pintype "power_in"))
      (node (ref "IC28") (pin "6") (pinfunction "VccB_6") (pintype "passive"))
      (node (ref "IC29") (pin "6") (pinfunction "VccB_6") (pintype "passive"))
      (node (ref "IC34") (pin "6") (pinfunction "VccB_6") (pintype "passive"))
      (node (ref "IC35") (pin "6") (pinfunction "VccB_6") (pintype "passive"))
      (node (ref "IC36") (pin "6") (pinfunction "VccB_6") (pintype "passive"))
      (node (ref "IC37") (pin "6") (pinfunction "VccB_6") (pintype "passive"))
      (node (ref "IC38") (pin "6") (pinfunction "VccB_6") (pintype "passive"))
      (node (ref "IC39") (pin "6") (pinfunction "VccB_6") (pintype "passive"))
      (node (ref "IC40") (pin "23") (pinfunction "VCCB_23") (pintype "power_in"))
      (node (ref "IC40") (pin "24") (pinfunction "VCCB_24") (pintype "power_in"))
      (node (ref "R309") (pin "1") (pinfunction "1_1") (pintype "passive"))
      (node (ref "R310") (pin "1") (pinfunction "1_1") (pintype "passive"))
    )
    (net (code "58") (name "unconnected-(IC22-1FSEN-Pad39)") (class "Default")
      (node (ref "IC22") (pin "39") (pinfunction "1FSEN_39") (pintype "input"))
    )
    (net (code "59") (name "unconnected-(IC22-2FSEN-Pad41)") (class "Default")
      (node (ref "IC22") (pin "41") (pinfunction "2FSEN_41") (pintype "input"))
    )
    (net (code "60") (name "unconnected-(IC22-3FSEN-Pad20)") (class "Default")
      (node (ref "IC22") (pin "20") (pinfunction "3FSEN_20") (pintype "input"))
    )
    (net (code "61") (name "unconnected-(IC22-4FSEN-Pad22)") (class "Default")
      (node (ref "IC22") (pin "22") (pinfunction "4FSEN_22") (pintype "input"))
    )
    (net (code "62") (name "unconnected-(IC22-nc-Pad17)") (class "Default")
      (node (ref "IC22") (pin "17") (pinfunction "nc_17") (pintype "passive"))
    )
    (net (code "63") (name "unconnected-(IC22-nc-Pad44)") (class "Default")
      (node (ref "IC22") (pin "44") (pinfunction "nc_44") (pintype "power_in"))
    )
    (net (code "64") (name "unconnected-(IC23-1FSEN-Pad39)") (class "Default")
      (node (ref "IC23") (pin "39") (pinfunction "1FSEN_39") (pintype "input"))
    )
    (net (code "65") (name "unconnected-(IC23-2FSEN-Pad41)") (class "Default")
      (node (ref "IC23") (pin "41") (pinfunction "2FSEN_41") (pintype "input"))
    )
    (net (code "66") (name "unconnected-(IC23-3FSEN-Pad20)") (class "Default")
      (node (ref "IC23") (pin "20") (pinfunction "3FSEN_20") (pintype "input"))
    )
    (net (code "67") (name "unconnected-(IC23-4FSEN-Pad22)") (class "Default")
      (node (ref "IC23") (pin "22") (pinfunction "4FSEN_22") (pintype "input"))
    )
    (net (code "68") (name "unconnected-(IC23-nc-Pad17)") (class "Default")
      (node (ref "IC23") (pin "17") (pinfunction "nc_17") (pintype "passive"))
    )
    (net (code "69") (name "unconnected-(IC23-nc-Pad44)") (class "Default")
      (node (ref "IC23") (pin "44") (pinfunction "nc_44") (pintype "power_in"))
    )
  )
)
